# Buck_Reg.net
KiCad netlist of a schematic drawn in Altium Designer
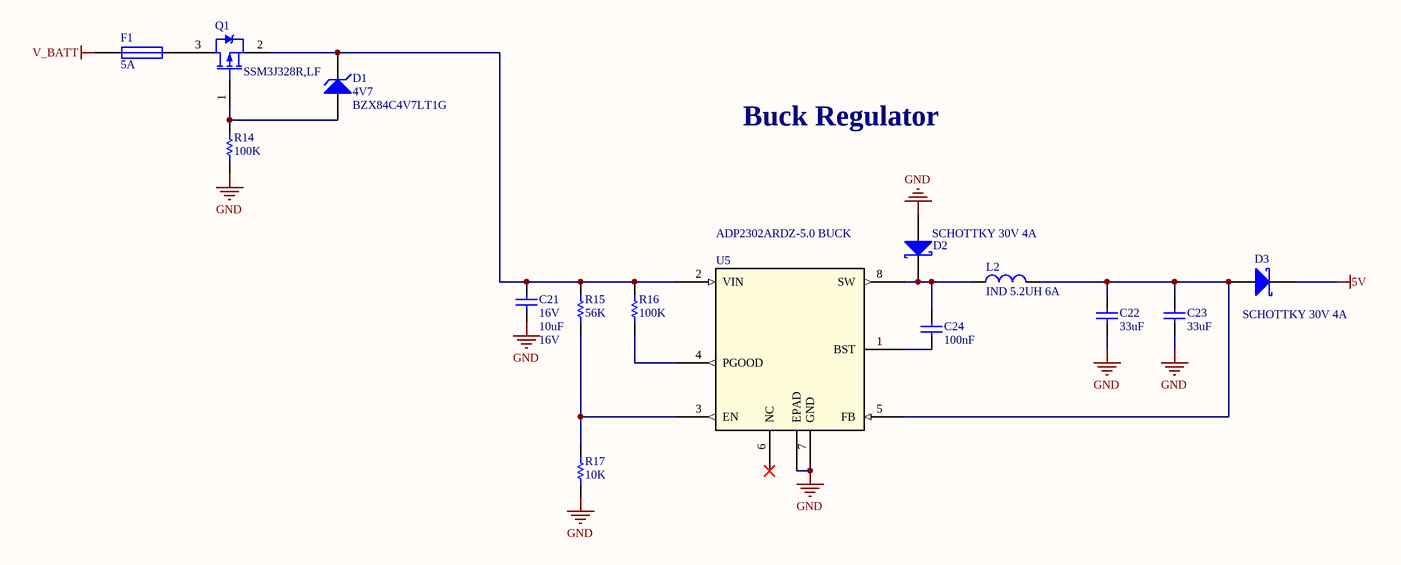
[diagram p0: Buck_Reg.SchDoc]

(export (version "E")
  (design (tool "Eeschema 10.0.6"))
  (components
    (comp (ref "C21")
      (value "10uF")
      (footprint "CAPC2012L")
      (description "CAP CER 10uF X5R 16V 0805")
      (fields
        (field (name "MANUFACTURER") "Samsung Electro-Mechanics")
        (field (name "MANUFACTURER PART NUMBER") "CL21A106KOQNNWE")
        (field (name "VOLTAGE - RATED") "16V")
        (field (name "MAX VOLTAGE") "16V")
      )
      (libsource (lib "ENCE461AD19_19V2") (part "CC_10uF_16V_0805"))
    )
    (comp (ref "C22")
      (value "33uF")
      (footprint "CAPC2012L")
      (description "CAP CER 33uF X5R 6V3 0805")
      (fields
        (field (name "MANUFACTURER") "TDK Corporation")
        (field (name "MANUFACTURER PART NUMBER") "C2012X5R0J336M125AC")
      )
      (libsource (lib "ENCE461AD19_19V2") (part "CC_33uF_6V3_0805"))
    )
    (comp (ref "C23")
      (value "33uF")
      (footprint "CAPC2012L")
      (description "CAP CER 33uF X5R 6V3 0805")
      (fields
        (field (name "MANUFACTURER") "TDK Corporation")
        (field (name "MANUFACTURER PART NUMBER") "C2012X5R0J336M125AC")
      )
      (libsource (lib "ENCE461AD19_19V2") (part "CC_33uF_6V3_0805"))
    )
    (comp (ref "C24")
      (value "100nF")
      (footprint "CAPC1608L")
      (description "CAP CER 100nF X7R +-10% 50V 0603")
      (libsource (lib "ECE AD19Components_19V1") (part "CC_100nF_0603"))
    )
    (comp (ref "D1")
      (value "4V7")
      (footprint "SOT23_L")
      (description "BZX84C4V7LT1G - DIODE, ZENER, 4.7V, 225MW, SOT23")
      (fields
        (field (name "MANUFACTURER") "ON SEMICONDUCTOR")
        (field (name "MANUFACTURER PART NUMBER") "BZX84C4V7LT1G")
      )
      (libsource (lib "ECE AD19Components_19V1") (part "DZ_4.7V"))
    )
    (comp (ref "D2")
      (value "SCHOTTKY 30V 4A")
      (footprint "SMC")
      (description "DIODE SCHOTTKY 30V 4A SMC")
      (fields
        (field (name "MANUFACTURER") "ON Semiconductor")
        (field (name "MANUFACTURER PART NUMBER") "MBRS330T3G")
      )
      (libsource (lib "ENCE461AD19_19V2") (part "MBRS330T3G"))
    )
    (comp (ref "D3")
      (value "SCHOTTKY 30V 4A")
      (footprint "SMC")
      (description "DIODE SCHOTTKY 30V 4A SMC")
      (fields
        (field (name "MANUFACTURER") "ON Semiconductor")
        (field (name "MANUFACTURER PART NUMBER") "MBRS330T3G")
      )
      (libsource (lib "ENCE461AD19_19V2") (part "MBRS330T3G"))
    )
    (comp (ref "F1")
      (value "5A")
      (footprint "RESC3216N")
      (description "Fuse 5.0A Fast Acting 1206 SMD")
      (fields (field (name "MANUFACTURER PART NUMBER") "C1F5") (field (name "MANUFACTURER") "Bel TRP"))
      (libsource (lib "ECE AD19Components_19V1") (part "FS_Fuse_5.0A"))
    )
    (comp (ref "L2")
      (value "IND 5.2UH 6A")
      (footprint "INDUCTOR5u2")
      (description "FIXED IND 5.2UH 6A 22 MOHM SMD")
      (fields
        (field (name "MANUFACTURER") "Sumida America Components Inc.")
        (field (name "MANUFACTURER PART NUMBER") "CDRH104RNP-5R2NC")
      )
      (libsource (lib "ENCE461AD19_19V2") (part "CDRH104RNP-5R2NC"))
    )
    (comp (ref "Q1")
      (value "SSM3J328R,LF")
      (footprint "SOT23_L")
      (description "MOSFET P-CH 20V 6A SOT23-3")
      (fields
        (field (name "MANUFACTURER") "Toshiba")
        (field (name "MANUFACTURER PART NUMBER") "SSM3J328R,LF")
      )
      (libsource (lib "ECE AD19Components_19V1") (part "TM_SSM3J328R"))
    )
    (comp (ref "R14")
      (value "100K")
      (footprint "RESC1608L")
      (description "RES 100K OHM 1/10W 5% 0603 SMD")
      (libsource (lib "ECE AD19Components_19V1") (part "RS_100K"))
    )
    (comp (ref "R15")
      (value "56K")
      (footprint "RESC1608L")
      (description "RES 56.0K OHM 1/10W 5% 0603 SMD")
      (libsource (lib "ECE AD19Components_19V1") (part "RS_56K"))
    )
    (comp (ref "R16")
      (value "100K")
      (footprint "RESC1608L")
      (description "RES 100K OHM 1/10W 5% 0603 SMD")
      (libsource (lib "ECE AD19Components_19V1") (part "RS_100K"))
    )
    (comp (ref "R17")
      (value "10K")
      (footprint "RESC1608L")
      (description "RES 10.0K OHM 1/10W 5% 0603 SMD")
      (libsource (lib "ECE AD19Components_19V1") (part "RS_10K"))
    )
    (comp (ref "U5")
      (value "ADP2302ARDZ-5.0 BUCK")
      (footprint "RD_8_1")
      (description "IC REG BUCK 5V 2A 8SOIC")
      (fields (field (name "MANUFACTURER_PART_NUMBER") "ADP2302ARDZ-5.0-R7"))
      (libsource (lib "ENCE461AD19_19V2") (part "ADP2302ARDZ-5.0-R7"))
    )
  )
  (nets
    (net (code "1") (name "5V") (class "Default")
      (node (ref "D3") (pin "2") (pinfunction "K_2") (pintype "passive"))
    )
    (net (code "2") (name "GND") (class "Default")
      (node (ref "C21") (pin "1") (pinfunction "1_1") (pintype "passive"))
      (node (ref "C22") (pin "1") (pinfunction "1_1") (pintype "passive"))
      (node (ref "C23") (pin "1") (pinfunction "1_1") (pintype "passive"))
      (node (ref "D2") (pin "1") (pinfunction "A_1") (pintype "passive"))
      (node (ref "R14") (pin "1") (pinfunction "1_1") (pintype "passive"))
      (node (ref "R17") (pin "1") (pinfunction "1_1") (pintype "passive"))
      (node (ref "U5") (pin "7") (pinfunction "GND_7") (pintype "power_in"))
      (node (ref "U5") (pin "EPAD") (pinfunction "EPAD_EPAD") (pintype "passive"))
    )
    (net (code "3") (name "Net-(D1-A)") (class "Default")
      (node (ref "D1") (pin "1") (pinfunction "A_1") (pintype "passive"))
      (node (ref "Q1") (pin "1") (pinfunction "1_1") (pintype "passive"))
      (node (ref "R14") (pin "2") (pinfunction "2_2") (pintype "passive"))
    )
    (net (code "4") (name "Net-(D1-K)") (class "Default")
      (node (ref "C21") (pin "2") (pinfunction "2_2") (pintype "passive"))
      (node (ref "D1") (pin "3") (pinfunction "K_3") (pintype "passive"))
      (node (ref "Q1") (pin "2") (pinfunction "2_2") (pintype "passive"))
      (node (ref "R15") (pin "2") (pinfunction "2_2") (pintype "passive"))
      (node (ref "R16") (pin "2") (pinfunction "2_2") (pintype "passive"))
      (node (ref "U5") (pin "2") (pinfunction "VIN_2") (pintype "input"))
    )
    (net (code "5") (name "Net-(D2-K)") (class "Default")
      (node (ref "C24") (pin "2") (pinfunction "2_2") (pintype "passive"))
      (node (ref "D2") (pin "2") (pinfunction "K_2") (pintype "passive"))
      (node (ref "L2") (pin "1") (pintype "passive"))
      (node (ref "U5") (pin "8") (pinfunction "SW_8") (pintype "output"))
    )
    (net (code "6") (name "Net-(D3-A)") (class "Default")
      (node (ref "C22") (pin "2") (pinfunction "2_2") (pintype "passive"))
      (node (ref "C23") (pin "2") (pinfunction "2_2") (pintype "passive"))
      (node (ref "D3") (pin "1") (pinfunction "A_1") (pintype "passive"))
      (node (ref "L2") (pin "2") (pintype "passive"))
      (node (ref "U5") (pin "5") (pinfunction "FB_5") (pintype "input"))
    )
    (net (code "7") (name "Net-(F1-Pad2)") (class "Default")
      (node (ref "F1") (pin "2") (pinfunction "2_2") (pintype "passive"))
      (node (ref "Q1") (pin "3") (pinfunction "3_3") (pintype "passive"))
    )
    (net (code "8") (name "Net-(U5-BST)") (class "Default")
      (node (ref "C24") (pin "1") (pinfunction "1_1") (pintype "passive"))
      (node (ref "U5") (pin "1") (pinfunction "BST_1") (pintype "passive"))
    )
    (net (code "9") (name "Net-(U5-EN)") (class "Default")
      (node (ref "R15") (pin "1") (pinfunction "1_1") (pintype "passive"))
      (node (ref "R17") (pin "2") (pinfunction "2_2") (pintype "passive"))
      (node (ref "U5") (pin "3") (pinfunction "EN_3") (pintype "output"))
    )
    (net (code "10") (name "Net-(U5-PGOOD)") (class "Default")
      (node (ref "R16") (pin "1") (pinfunction "1_1") (pintype "passive"))
      (node (ref "U5") (pin "4") (pinfunction "PGOOD_4") (pintype "output"))
    )
    (net (code "11") (name "V_BATT") (class "Default")
      (node (ref "F1") (pin "1") (pinfunction "1_1") (pintype "passive"))
    )
    (net (code "12") (name "unconnected-(U5-NC-Pad6)") (class "Default")
      (node (ref "U5") (pin "6") (pinfunction "NC_6") (pintype "passive+no_connect"))
    )
  )
)
